# barduino.net
KiCad netlist of a schematic drawn in EAGLE
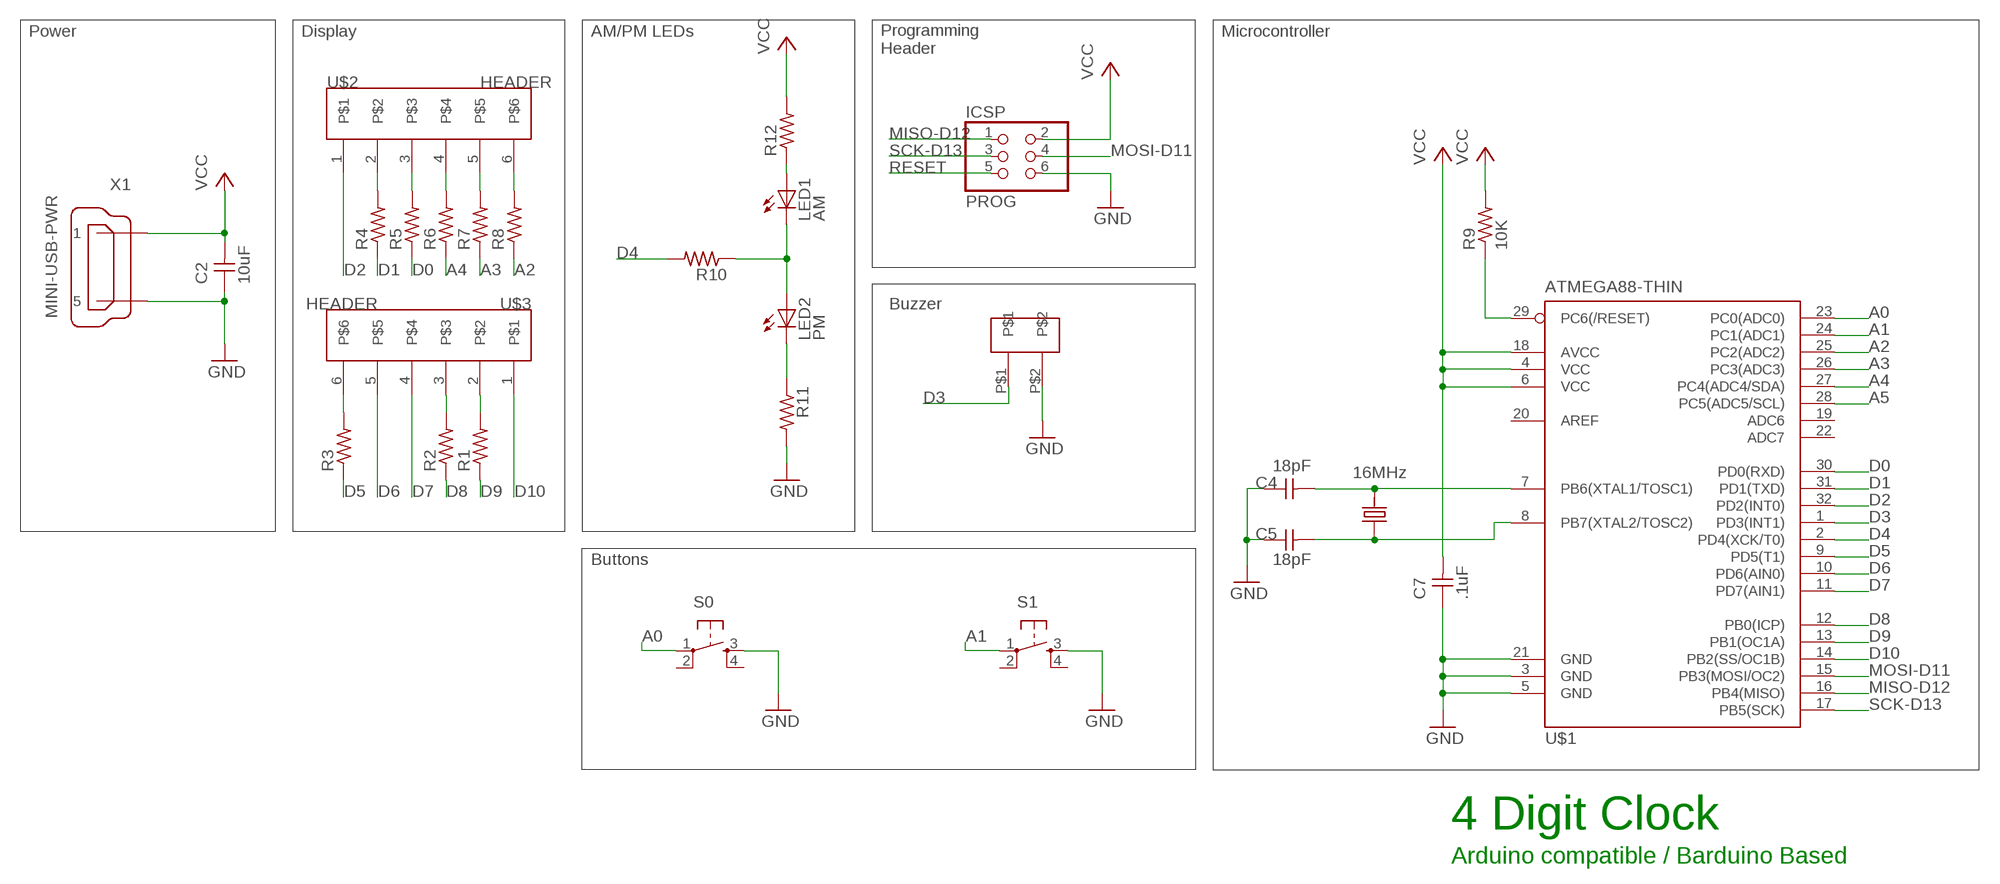
[diagram p0: schematic, sheet 1]

(export (version "E")
  (design (tool "Eeschema 10.0.6"))
  (components
    (comp (ref "C2")
      (value "10uF")
      (footprint "eagle-import:1206")
      (libsource (lib "eagle-import") (part "UNPOLARIZED_CAPACITOR1206"))
    )
    (comp (ref "C4")
      (value "18pF")
      (footprint "eagle-import:1206")
      (libsource (lib "eagle-import") (part "UNPOLARIZED_CAPACITOR1206"))
    )
    (comp (ref "C5")
      (value "18pF")
      (footprint "eagle-import:1206")
      (libsource (lib "eagle-import") (part "UNPOLARIZED_CAPACITOR1206"))
    )
    (comp (ref "C7")
      (value ".1uF")
      (footprint "eagle-import:1206")
      (libsource (lib "eagle-import") (part "UNPOLARIZED_CAPACITOR1206"))
    )
    (comp (ref "ICSP")
      (value "PROG")
      (footprint "eagle-import:2X03SMD")
      (libsource (lib "eagle-import") (part "PINHD-2X3-SMD"))
    )
    (comp (ref "LED1")
      (value "AM")
      (footprint "eagle-import:CHIPLED_1206")
      (libsource (lib "eagle-import") (part "LEDCHIPLED_1206"))
    )
    (comp (ref "LED2")
      (value "PM")
      (footprint "eagle-import:CHIPLED_1206")
      (libsource (lib "eagle-import") (part "LEDCHIPLED_1206"))
    )
    (comp (ref "Q2")
      (value "16MHz")
      (footprint "eagle-import:CS10")
      (libsource (lib "eagle-import") (part "CRYSTALCS10"))
    )
    (comp (ref "R1")
      (value "R-US_R1206")
      (footprint "eagle-import:R1206")
      (libsource (lib "eagle-import") (part "R-US_R1206"))
    )
    (comp (ref "R2")
      (value "R-US_R1206")
      (footprint "eagle-import:R1206")
      (libsource (lib "eagle-import") (part "R-US_R1206"))
    )
    (comp (ref "R3")
      (value "R-US_R1206")
      (footprint "eagle-import:R1206")
      (libsource (lib "eagle-import") (part "R-US_R1206"))
    )
    (comp (ref "R4")
      (value "R-US_R1206")
      (footprint "eagle-import:R1206")
      (libsource (lib "eagle-import") (part "R-US_R1206"))
    )
    (comp (ref "R5")
      (value "R-US_R1206")
      (footprint "eagle-import:R1206")
      (libsource (lib "eagle-import") (part "R-US_R1206"))
    )
    (comp (ref "R6")
      (value "R-US_R1206")
      (footprint "eagle-import:R1206")
      (libsource (lib "eagle-import") (part "R-US_R1206"))
    )
    (comp (ref "R7")
      (value "R-US_R1206")
      (footprint "eagle-import:R1206")
      (libsource (lib "eagle-import") (part "R-US_R1206"))
    )
    (comp (ref "R8")
      (value "R-US_R1206")
      (footprint "eagle-import:R1206")
      (libsource (lib "eagle-import") (part "R-US_R1206"))
    )
    (comp (ref "R9")
      (value "10K")
      (footprint "eagle-import:1206")
      (libsource (lib "eagle-import") (part "RESISTOR1206"))
    )
    (comp (ref "R10")
      (value "R-US_R1206")
      (footprint "eagle-import:R1206")
      (libsource (lib "eagle-import") (part "R-US_R1206"))
    )
    (comp (ref "R11")
      (value "R-US_R1206")
      (footprint "eagle-import:R1206")
      (libsource (lib "eagle-import") (part "R-US_R1206"))
    )
    (comp (ref "R12")
      (value "R-US_R1206")
      (footprint "eagle-import:R1206")
      (libsource (lib "eagle-import") (part "R-US_R1206"))
    )
    (comp (ref "S0")
      (value "6MM_SWITCH6MM_SWITCH")
      (footprint "eagle-import:6MM_SWITCH")
      (libsource (lib "eagle-import") (part "6MM_SWITCH6MM_SWITCH"))
    )
    (comp (ref "S1")
      (value "6MM_SWITCH6MM_SWITCH")
      (footprint "eagle-import:6MM_SWITCH")
      (libsource (lib "eagle-import") (part "6MM_SWITCH6MM_SWITCH"))
    )
    (comp (ref "U$1")
      (value "ATMEGA88-THIN")
      (footprint "eagle-import:TQFP32-08THIN")
      (libsource (lib "eagle-import") (part "ATMEGA88-THIN"))
    )
    (comp (ref "U$2")
      (value "HEADER")
      (footprint "eagle-import:HEADER")
      (libsource (lib "eagle-import") (part "HEADER"))
    )
    (comp (ref "U$3")
      (value "HEADER")
      (footprint "eagle-import:HEADER")
      (libsource (lib "eagle-import") (part "HEADER"))
    )
    (comp (ref "U$4")
      (value "BUZZER")
      (footprint "eagle-import:BUZZER")
      (libsource (lib "eagle-import") (part "BUZZER"))
    )
    (comp (ref "X1")
      (value "MINI-USB-PWR")
      (footprint "eagle-import:UX60-MB-5ST-PWR")
      (libsource (lib "eagle-import") (part "MINI-USB-PWR"))
    )
  )
  (nets
    (net (code "1") (name "/A0") (class "Default")
      (node (ref "S0") (pin "1") (pinfunction "P_1") (pintype "passive"))
      (node (ref "U$1") (pin "23") (pinfunction "PC0(ADC0)_23") (pintype "bidirectional"))
    )
    (net (code "2") (name "/A1") (class "Default")
      (node (ref "S1") (pin "1") (pinfunction "P_1") (pintype "passive"))
      (node (ref "U$1") (pin "24") (pinfunction "PC1(ADC1)_24") (pintype "bidirectional"))
    )
    (net (code "3") (name "/A2") (class "Default")
      (node (ref "R8") (pin "1") (pinfunction "1_1") (pintype "passive"))
      (node (ref "U$1") (pin "25") (pinfunction "PC2(ADC2)_25") (pintype "bidirectional"))
    )
    (net (code "4") (name "/A3") (class "Default")
      (node (ref "R7") (pin "1") (pinfunction "1_1") (pintype "passive"))
      (node (ref "U$1") (pin "26") (pinfunction "PC3(ADC3)_26") (pintype "bidirectional"))
    )
    (net (code "5") (name "/A4") (class "Default")
      (node (ref "R6") (pin "1") (pinfunction "1_1") (pintype "passive"))
      (node (ref "U$1") (pin "27") (pinfunction "PC4(ADC4/SDA)_27") (pintype "bidirectional"))
    )
    (net (code "6") (name "/A5") (class "Default")
      (node (ref "U$1") (pin "28") (pinfunction "PC5(ADC5/SCL)_28") (pintype "bidirectional"))
    )
    (net (code "7") (name "/D0") (class "Default")
      (node (ref "R5") (pin "1") (pinfunction "1_1") (pintype "passive"))
      (node (ref "U$1") (pin "30") (pinfunction "PD0(RXD)_30") (pintype "bidirectional"))
    )
    (net (code "8") (name "/D1") (class "Default")
      (node (ref "R4") (pin "1") (pinfunction "1_1") (pintype "passive"))
      (node (ref "U$1") (pin "31") (pinfunction "PD1(TXD)_31") (pintype "bidirectional"))
    )
    (net (code "9") (name "/D2") (class "Default")
      (node (ref "U$1") (pin "32") (pinfunction "PD2(INT0)_32") (pintype "bidirectional"))
      (node (ref "U$2") (pin "1") (pinfunction "P$1_1") (pintype "bidirectional"))
    )
    (net (code "10") (name "/D3") (class "Default")
      (node (ref "U$1") (pin "1") (pinfunction "PD3(INT1)_1") (pintype "bidirectional"))
      (node (ref "U$4") (pin "P$1") (pinfunction "P$1_P$1") (pintype "bidirectional"))
    )
    (net (code "11") (name "/D4") (class "Default")
      (node (ref "R10") (pin "2") (pinfunction "2_2") (pintype "passive"))
      (node (ref "U$1") (pin "2") (pinfunction "PD4(XCK/T0)_2") (pintype "bidirectional"))
    )
    (net (code "12") (name "/D5") (class "Default")
      (node (ref "R3") (pin "1") (pinfunction "1_1") (pintype "passive"))
      (node (ref "U$1") (pin "9") (pinfunction "PD5(T1)_9") (pintype "bidirectional"))
    )
    (net (code "13") (name "/D6") (class "Default")
      (node (ref "U$1") (pin "10") (pinfunction "PD6(AIN0)_10") (pintype "bidirectional"))
      (node (ref "U$3") (pin "5") (pinfunction "P$5_5") (pintype "bidirectional"))
    )
    (net (code "14") (name "/D7") (class "Default")
      (node (ref "U$1") (pin "11") (pinfunction "PD7(AIN1)_11") (pintype "bidirectional"))
      (node (ref "U$3") (pin "4") (pinfunction "P$4_4") (pintype "bidirectional"))
    )
    (net (code "15") (name "/D8") (class "Default")
      (node (ref "R2") (pin "1") (pinfunction "1_1") (pintype "passive"))
      (node (ref "U$1") (pin "12") (pinfunction "PB0(ICP)_12") (pintype "bidirectional"))
    )
    (net (code "16") (name "/D9") (class "Default")
      (node (ref "R1") (pin "1") (pinfunction "1_1") (pintype "passive"))
      (node (ref "U$1") (pin "13") (pinfunction "PB1(OC1A)_13") (pintype "bidirectional"))
    )
    (net (code "17") (name "/D10") (class "Default")
      (node (ref "U$1") (pin "14") (pinfunction "PB2(SS/OC1B)_14") (pintype "bidirectional"))
      (node (ref "U$3") (pin "1") (pinfunction "P$1_1") (pintype "bidirectional"))
    )
    (net (code "18") (name "/MISO-D12") (class "Default")
      (node (ref "ICSP") (pin "1") (pinfunction "1_1") (pintype "passive"))
      (node (ref "U$1") (pin "16") (pinfunction "PB4(MISO)_16") (pintype "bidirectional"))
    )
    (net (code "19") (name "/MOSI-D11") (class "Default")
      (node (ref "ICSP") (pin "4") (pinfunction "4_4") (pintype "passive"))
      (node (ref "U$1") (pin "15") (pinfunction "PB3(MOSI/OC2)_15") (pintype "bidirectional"))
    )
    (net (code "20") (name "/RESET") (class "Default")
      (node (ref "ICSP") (pin "5") (pinfunction "5_5") (pintype "passive"))
      (node (ref "R9") (pin "1") (pinfunction "1_1") (pintype "passive"))
      (node (ref "U$1") (pin "29") (pinfunction "PC6(/RESET)_29") (pintype "bidirectional"))
    )
    (net (code "21") (name "/SCK-D13") (class "Default")
      (node (ref "ICSP") (pin "3") (pinfunction "3_3") (pintype "passive"))
      (node (ref "U$1") (pin "17") (pinfunction "PB5(SCK)_17") (pintype "bidirectional"))
    )
    (net (code "22") (name "GND") (class "Default")
      (node (ref "C2") (pin "1") (pinfunction "1_1") (pintype "passive"))
      (node (ref "C4") (pin "1") (pinfunction "1_1") (pintype "passive"))
      (node (ref "C5") (pin "1") (pinfunction "1_1") (pintype "passive"))
      (node (ref "C7") (pin "1") (pinfunction "1_1") (pintype "passive"))
      (node (ref "ICSP") (pin "6") (pinfunction "6_6") (pintype "passive"))
      (node (ref "R11") (pin "2") (pinfunction "2_2") (pintype "passive"))
      (node (ref "S0") (pin "3") (pinfunction "S_3") (pintype "passive"))
      (node (ref "S1") (pin "3") (pinfunction "S_3") (pintype "passive"))
      (node (ref "U$1") (pin "21") (pinfunction "GND_21") (pintype "power_in"))
      (node (ref "U$1") (pin "3") (pinfunction "GND_3") (pintype "power_in"))
      (node (ref "U$1") (pin "5") (pinfunction "GND_5") (pintype "power_in"))
      (node (ref "U$4") (pin "P$2") (pinfunction "P$2_P$2") (pintype "bidirectional"))
      (node (ref "X1") (pin "5") (pinfunction "5_5") (pintype "input"))
    )
    (net (code "23") (name "Net-(LED1-PadA)") (class "Default")
      (node (ref "LED1") (pin "A") (pinfunction "A_A") (pintype "passive"))
      (node (ref "R12") (pin "1") (pinfunction "1_1") (pintype "passive"))
    )
    (net (code "24") (name "Net-(LED1-PadC)") (class "Default")
      (node (ref "LED1") (pin "C") (pinfunction "C_C") (pintype "passive"))
      (node (ref "LED2") (pin "A") (pinfunction "A_A") (pintype "passive"))
      (node (ref "R10") (pin "1") (pinfunction "1_1") (pintype "passive"))
    )
    (net (code "25") (name "Net-(LED2-PadC)") (class "Default")
      (node (ref "LED2") (pin "C") (pinfunction "C_C") (pintype "passive"))
      (node (ref "R11") (pin "1") (pinfunction "1_1") (pintype "passive"))
    )
    (net (code "26") (name "Net-(Q2-1)") (class "Default")
      (node (ref "C5") (pin "2") (pinfunction "2_2") (pintype "passive"))
      (node (ref "Q2") (pin "P$1") (pinfunction "1_P$1") (pintype "passive"))
      (node (ref "U$1") (pin "8") (pinfunction "PB7(XTAL2/TOSC2)_8") (pintype "bidirectional"))
    )
    (net (code "27") (name "Net-(Q2-2)") (class "Default")
      (node (ref "C4") (pin "2") (pinfunction "2_2") (pintype "passive"))
      (node (ref "Q2") (pin "P$2") (pinfunction "2_P$2") (pintype "passive"))
      (node (ref "U$1") (pin "7") (pinfunction "PB6(XTAL1/TOSC1)_7") (pintype "bidirectional"))
    )
    (net (code "28") (name "Net-(U$2-P$2)") (class "Default")
      (node (ref "R4") (pin "2") (pinfunction "2_2") (pintype "passive"))
      (node (ref "U$2") (pin "2") (pinfunction "P$2_2") (pintype "bidirectional"))
    )
    (net (code "29") (name "Net-(U$2-P$3)") (class "Default")
      (node (ref "R5") (pin "2") (pinfunction "2_2") (pintype "passive"))
      (node (ref "U$2") (pin "3") (pinfunction "P$3_3") (pintype "bidirectional"))
    )
    (net (code "30") (name "Net-(U$2-P$4)") (class "Default")
      (node (ref "R6") (pin "2") (pinfunction "2_2") (pintype "passive"))
      (node (ref "U$2") (pin "4") (pinfunction "P$4_4") (pintype "bidirectional"))
    )
    (net (code "31") (name "Net-(U$2-P$5)") (class "Default")
      (node (ref "R7") (pin "2") (pinfunction "2_2") (pintype "passive"))
      (node (ref "U$2") (pin "5") (pinfunction "P$5_5") (pintype "bidirectional"))
    )
    (net (code "32") (name "Net-(U$2-P$6)") (class "Default")
      (node (ref "R8") (pin "2") (pinfunction "2_2") (pintype "passive"))
      (node (ref "U$2") (pin "6") (pinfunction "P$6_6") (pintype "bidirectional"))
    )
    (net (code "33") (name "Net-(U$3-P$2)") (class "Default")
      (node (ref "R1") (pin "2") (pinfunction "2_2") (pintype "passive"))
      (node (ref "U$3") (pin "2") (pinfunction "P$2_2") (pintype "bidirectional"))
    )
    (net (code "34") (name "Net-(U$3-P$3)") (class "Default")
      (node (ref "R2") (pin "2") (pinfunction "2_2") (pintype "passive"))
      (node (ref "U$3") (pin "3") (pinfunction "P$3_3") (pintype "bidirectional"))
    )
    (net (code "35") (name "Net-(U$3-P$6)") (class "Default")
      (node (ref "R3") (pin "2") (pinfunction "2_2") (pintype "passive"))
      (node (ref "U$3") (pin "6") (pinfunction "P$6_6") (pintype "bidirectional"))
    )
    (net (code "36") (name "VCC") (class "Default")
      (node (ref "C2") (pin "2") (pinfunction "2_2") (pintype "passive"))
      (node (ref "C7") (pin "2") (pinfunction "2_2") (pintype "passive"))
      (node (ref "ICSP") (pin "2") (pinfunction "2_2") (pintype "passive"))
      (node (ref "R12") (pin "2") (pinfunction "2_2") (pintype "passive"))
      (node (ref "R9") (pin "2") (pinfunction "2_2") (pintype "passive"))
      (node (ref "U$1") (pin "18") (pinfunction "AVCC_18") (pintype "power_in"))
      (node (ref "U$1") (pin "4") (pinfunction "VCC_4") (pintype "power_in"))
      (node (ref "U$1") (pin "6") (pinfunction "VCC_6") (pintype "power_in"))
      (node (ref "X1") (pin "1") (pinfunction "1_1") (pintype "input"))
    )
    (net (code "37") (name "unconnected-(S0-P1-Pad2)") (class "Default")
      (node (ref "S0") (pin "2") (pinfunction "P1_2") (pintype "passive"))
    )
    (net (code "38") (name "unconnected-(S0-S1-Pad4)") (class "Default")
      (node (ref "S0") (pin "4") (pinfunction "S1_4") (pintype "passive"))
    )
    (net (code "39") (name "unconnected-(S1-P1-Pad2)") (class "Default")
      (node (ref "S1") (pin "2") (pinfunction "P1_2") (pintype "passive"))
    )
    (net (code "40") (name "unconnected-(S1-S1-Pad4)") (class "Default")
      (node (ref "S1") (pin "4") (pinfunction "S1_4") (pintype "passive"))
    )
    (net (code "41") (name "unconnected-(U$1-ADC6-Pad19)") (class "Default")
      (node (ref "U$1") (pin "19") (pinfunction "ADC6_19") (pintype "bidirectional"))
    )
    (net (code "42") (name "unconnected-(U$1-ADC7-Pad22)") (class "Default")
      (node (ref "U$1") (pin "22") (pinfunction "ADC7_22") (pintype "bidirectional"))
    )
    (net (code "43") (name "unconnected-(U$1-AREF-Pad20)") (class "Default")
      (node (ref "U$1") (pin "20") (pinfunction "AREF_20") (pintype "passive"))
    )
  )
)
